# Barreira_pacote.net
KiCad netlist of a schematic drawn in Altium Designer
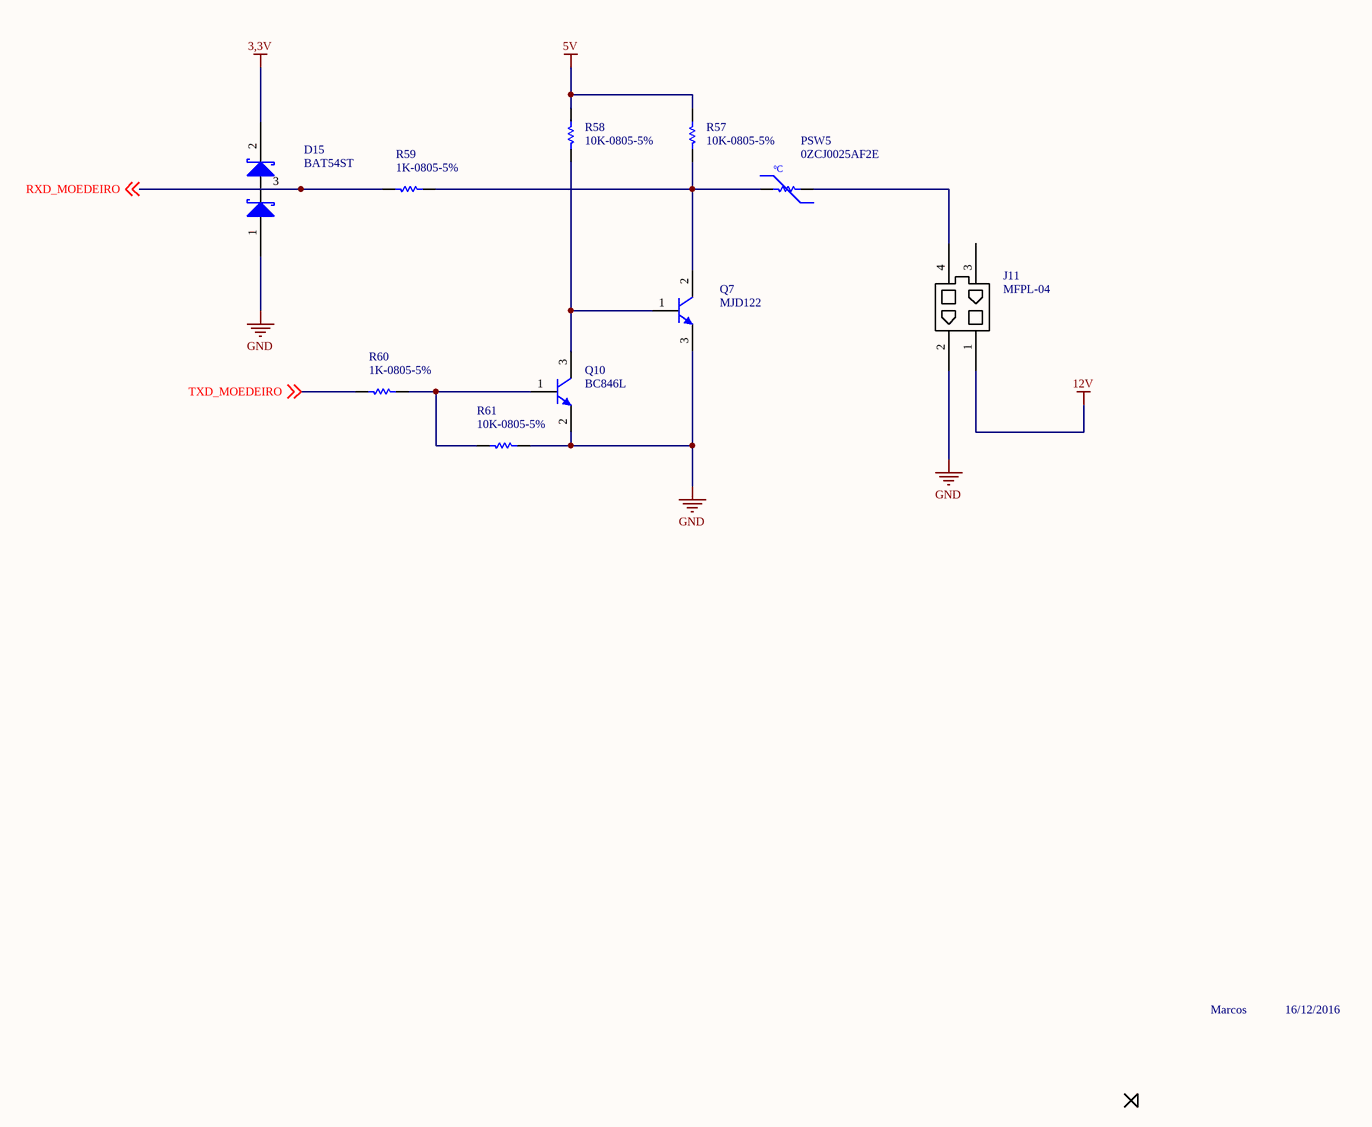
[diagram p0: Barreira_pacote.SchDoc]

(export (version "E")
  (design (tool "Eeschema 10.0.6"))
  (components
    (comp (ref "D15")
      (value "BAT54ST")
      (footprint "SOT23 - REVISADO ONDA")
      (libsource (lib "AquinoLib") (part "BAT54ST"))
    )
    (comp (ref "J11") (value "MFPL-04") (libsource (lib "AquinoLib") (part "MFPL-04")))
    (comp (ref "PSW5")
      (value "0ZCJ0025AF2E")
      (footprint "1206-REVISADO ONDA")
      (description "PTC 2A-120V")
      (libsource (lib "AquinoLib") (part "PTC 2A-120V"))
    )
    (comp (ref "Q7")
      (value "MJD122")
      (footprint "DPAK REVISADO ONDA")
      (description "MJD31")
      (libsource (lib "AquinoLib") (part "MJD31"))
    )
    (comp (ref "Q10")
      (value "BC846L")
      (footprint "SOT23 - REVISADO ONDA")
      (libsource (lib "AquinoLib") (part "BC846"))
    )
    (comp (ref "R57")
      (value "10K-0805-5%")
      (footprint "0805-REVISADO ONDA")
      (libsource (lib "AquinoLib") (part "10K-0805-5%"))
    )
    (comp (ref "R58")
      (value "10K-0805-5%")
      (footprint "0805-REVISADO ONDA")
      (libsource (lib "AquinoLib") (part "10K-0805-5%"))
    )
    (comp (ref "R59")
      (value "1K-0805-5%")
      (footprint "0805-REVISADO ONDA")
      (libsource (lib "AquinoLib") (part "1K-0805-5%"))
    )
    (comp (ref "R60")
      (value "1K-0805-5%")
      (footprint "0805-REVISADO ONDA")
      (libsource (lib "AquinoLib") (part "1K-0805-5%"))
    )
    (comp (ref "R61")
      (value "10K-0805-5%")
      (footprint "0805-REVISADO ONDA")
      (libsource (lib "AquinoLib") (part "10K-0805-5%"))
    )
  )
  (nets
    (net (code "1") (name "3,3V") (class "Default")
      (node (ref "D15") (pin "2") (pinfunction "2_2") (pintype "passive"))
    )
    (net (code "2") (name "5V") (class "Default")
      (node (ref "R57") (pin "2") (pinfunction "2_2") (pintype "passive"))
      (node (ref "R58") (pin "2") (pinfunction "2_2") (pintype "passive"))
    )
    (net (code "3") (name "12V") (class "Default")
      (node (ref "J11") (pin "1") (pinfunction "1_1") (pintype "passive"))
    )
    (net (code "4") (name "GND") (class "Default")
      (node (ref "D15") (pin "1") (pinfunction "1_1") (pintype "passive"))
      (node (ref "J11") (pin "2") (pinfunction "2_2") (pintype "passive"))
      (node (ref "Q10") (pin "2") (pinfunction "E_2") (pintype "passive"))
      (node (ref "Q7") (pin "3") (pinfunction "E_3") (pintype "passive"))
      (node (ref "R61") (pin "1") (pinfunction "1_1") (pintype "passive"))
    )
    (net (code "5") (name "Net-(J11-Pad4)") (class "Default")
      (node (ref "J11") (pin "4") (pinfunction "4_4") (pintype "passive"))
      (node (ref "PSW5") (pin "1") (pinfunction "1_1") (pintype "passive"))
    )
    (net (code "6") (name "Net-(Q7-C)") (class "Default")
      (node (ref "PSW5") (pin "2") (pinfunction "2_2") (pintype "passive"))
      (node (ref "Q7") (pin "2") (pinfunction "C_2") (pintype "passive"))
      (node (ref "R57") (pin "1") (pinfunction "1_1") (pintype "passive"))
      (node (ref "R59") (pin "1") (pinfunction "1_1") (pintype "passive"))
    )
    (net (code "7") (name "Net-(Q10-B)") (class "Default")
      (node (ref "Q10") (pin "1") (pinfunction "B_1") (pintype "passive"))
      (node (ref "R60") (pin "1") (pinfunction "1_1") (pintype "passive"))
      (node (ref "R61") (pin "2") (pinfunction "2_2") (pintype "passive"))
    )
    (net (code "8") (name "Net-(Q10-C)") (class "Default")
      (node (ref "Q10") (pin "3") (pinfunction "C_3") (pintype "passive"))
      (node (ref "Q7") (pin "1") (pinfunction "B_1") (pintype "passive"))
      (node (ref "R58") (pin "1") (pinfunction "1_1") (pintype "passive"))
    )
    (net (code "9") (name "RXD_MOEDEIRO") (class "Default")
      (node (ref "D15") (pin "3") (pinfunction "3_3") (pintype "passive"))
      (node (ref "R59") (pin "2") (pinfunction "2_2") (pintype "passive"))
    )
    (net (code "10") (name "TXD_MOEDEIRO") (class "Default")
      (node (ref "R60") (pin "2") (pinfunction "2_2") (pintype "passive"))
    )
    (net (code "11") (name "unconnected-(J11-Pad3)") (class "Default")
      (node (ref "J11") (pin "3") (pinfunction "3_3") (pintype "passive"))
    )
  )
)
